# PDOC.net
KiCad netlist of a schematic drawn in Altium Designer
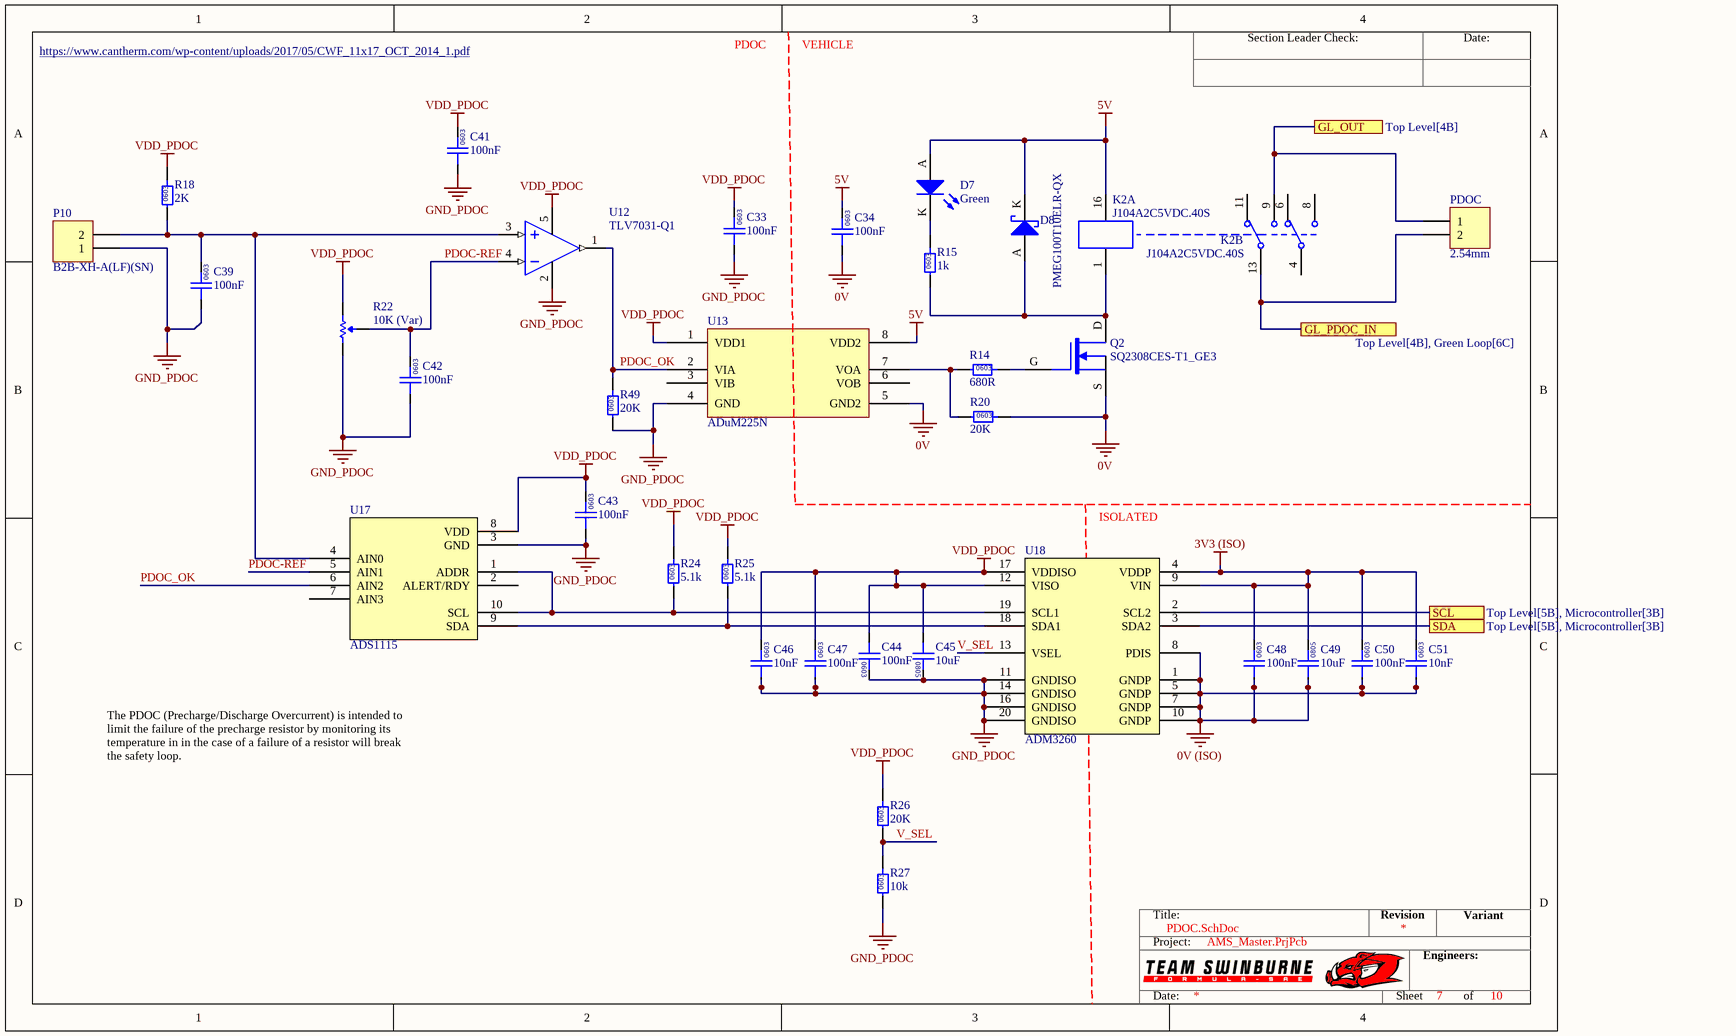
[diagram p0: PDOC.SchDoc]

(export (version "E")
  (design (tool "Eeschema 10.0.6"))
  (components
    (comp (ref "C33")
      (value "100nF")
      (footprint "0603")
      (fields
        (field (name "PART NUMBER") "CL10B104KC8NNNC")
        (field (name "MANUFACTURER") "Samsung Electro-Mechanics")
        (field (name "TOLERANCE") "±10%")
      )
      (libsource (lib "ts_standard_library") (part "Capacitor 0603"))
    )
    (comp (ref "C34")
      (value "100nF")
      (footprint "0603")
      (fields
        (field (name "PART NUMBER") "CL10B104KC8NNNC")
        (field (name "MANUFACTURER") "Samsung Electro-Mechanics")
        (field (name "TOLERANCE") "±10%")
      )
      (libsource (lib "ts_standard_library") (part "Capacitor 0603"))
    )
    (comp (ref "C39")
      (value "100nF")
      (footprint "0603")
      (fields
        (field (name "PART NUMBER") "GCM188L81H104KA57D")
        (field (name "MANUFACTURER") "muRata")
        (field (name "TOLERANCE") "±10%")
      )
      (libsource (lib "ts_standard_library") (part "Capacitor 0603"))
    )
    (comp (ref "C41")
      (value "100nF")
      (footprint "0603")
      (fields
        (field (name "PART NUMBER") "GCM188L81H104KA57D")
        (field (name "MANUFACTURER") "muRata")
        (field (name "TOLERANCE") "±10%")
      )
      (libsource (lib "ts_standard_library") (part "Capacitor 0603"))
    )
    (comp (ref "C42")
      (value "100nF")
      (footprint "0603")
      (fields
        (field (name "PART NUMBER") "GCM188L81H104KA57D")
        (field (name "MANUFACTURER") "muRata")
        (field (name "TOLERANCE") "±10%")
      )
      (libsource (lib "ts_standard_library") (part "Capacitor 0603"))
    )
    (comp (ref "C43")
      (value "100nF")
      (footprint "0603")
      (fields
        (field (name "PART NUMBER") "GCM188L81H104KA57D")
        (field (name "MANUFACTURER") "muRata")
        (field (name "TOLERANCE") "±10%")
      )
      (libsource (lib "ts_standard_library") (part "Capacitor 0603"))
    )
    (comp (ref "C44")
      (value "100nF")
      (footprint "0603")
      (fields
        (field (name "PART NUMBER") "GCM188L81H104KA57D")
        (field (name "MANUFACTURER") "muRata")
        (field (name "TOLERANCE") "±10%")
      )
      (libsource (lib "ts_standard_library") (part "Capacitor 0603"))
    )
    (comp (ref "C45")
      (value "10uF")
      (footprint "0805")
      (fields
        (field (name "PART NUMBER") "GRM21BR6YA106KE43L")
        (field (name "MANUFACTURER") "muRata")
        (field (name "TOLERANCE") "10%")
      )
      (libsource (lib "ts_standard_library") (part "Capacitor 0805"))
    )
    (comp (ref "C46")
      (value "10nF")
      (footprint "0603")
      (fields
        (field (name "PART NUMBER") "GCM188L81H103KA03D")
        (field (name "MANUFACTURER") "muRata")
        (field (name "TOLERANCE") "±10%")
      )
      (libsource (lib "ts_standard_library") (part "Capacitor 0603"))
    )
    (comp (ref "C47")
      (value "100nF")
      (footprint "0603")
      (fields
        (field (name "PART NUMBER") "GCM188L81H104KA57D")
        (field (name "MANUFACTURER") "muRata")
        (field (name "TOLERANCE") "±10%")
      )
      (libsource (lib "ts_standard_library") (part "Capacitor 0603"))
    )
    (comp (ref "C48")
      (value "100nF")
      (footprint "0603")
      (fields
        (field (name "PART NUMBER") "GCM188L81H104KA57D")
        (field (name "MANUFACTURER") "muRata")
        (field (name "TOLERANCE") "±10%")
      )
      (libsource (lib "ts_standard_library") (part "Capacitor 0603"))
    )
    (comp (ref "C49")
      (value "10uF")
      (footprint "0805")
      (fields
        (field (name "PART NUMBER") "GRM21BR6YA106KE43L")
        (field (name "MANUFACTURER") "muRata")
        (field (name "TOLERANCE") "10%")
      )
      (libsource (lib "ts_standard_library") (part "Capacitor 0805"))
    )
    (comp (ref "C50")
      (value "100nF")
      (footprint "0603")
      (fields
        (field (name "PART NUMBER") "GCM188L81H104KA57D")
        (field (name "MANUFACTURER") "muRata")
        (field (name "TOLERANCE") "±10%")
      )
      (libsource (lib "ts_standard_library") (part "Capacitor 0603"))
    )
    (comp (ref "C51")
      (value "10nF")
      (footprint "0603")
      (fields
        (field (name "PART NUMBER") "GCM188L81H103KA03D")
        (field (name "MANUFACTURER") "muRata")
        (field (name "TOLERANCE") "±10%")
      )
      (libsource (lib "ts_standard_library") (part "Capacitor 0603"))
    )
    (comp (ref "D7")
      (value "Green")
      (footprint "0805 LED")
      (description "Green LED Indication - Discrete 1.75V 0805 (2012 Metric)")
      (fields (field (name "PART NUMBER") "SML-210FTT86") (field (name "MANUFACTURER") "ROHM Semiconductor"))
      (libsource (lib "ts_20-standard-library") (part "LED"))
    )
    (comp (ref "D8")
      (value "PMEG100T10ELR-QX")
      (footprint "NXP SOD123W")
      (fields
        (field (name "MANUFACTURER") "Nexperia USA Inc.")
        (field (name "DIGIKEY PART NUMBER") "1727-PMEG100T10ELR-QXCT-ND")
      )
      (libsource (lib "ts_standard_library") (part "Diode (Schottky)"))
    )
    (comp (ref "K2")
      (value "J104A2C5VDC.40S")
      (footprint "TI 2-DIL")
      (description "RELAY GEN PURPOSE DPDT 3A 5V")
      (fields
        (field (name "MANUFACTURER") "CIT Relay and Switch")
        (field (name "DIGIKEY PART NUMBER") "2449-J104A2C5VDC.40S-ND")
      )
      (libsource (lib "") (part "J104A2C5VDC.40S_1"))
    )
    (comp (ref "P10")
      (value "B2B-XH-A(LF)(SN)")
      (footprint "XH 2 PIN VERT")
      (fields (field (name "DIGIKEY PART NUMBER") "455-2247-ND") (field (name "CONTACT") "Tin"))
      (libsource (lib "ts_standard_connectors") (part "Header 1x2"))
    )
    (comp (ref "PDOC")
      (value "2.54mm")
      (footprint "TH 2.54mm Header 1x2")
      (fields (field (name "PART NUMBER") "TH 2.54mm Header 1x2") (field (name "CONTACT") "NA"))
      (libsource (lib "") (part "Header 1x2_1"))
    )
    (comp (ref "Q2")
      (value "SQ2308CES-T1_GE3")
      (footprint "VSHY SOT-23-3")
      (description "MOSFET N-CH 60V 2.3A SOT23")
      (fields
        (field (name "MANUFACTURER") "Vishay Siliconix")
        (field (name "DIGIKEY PART NUMBER") "SQ2308CES-T1_GE3CT-ND")
        (field (name "PUBLISHER") "Altium Limited")
      )
      (libsource (lib "ts_standard_library") (part "MOSFET-N"))
    )
    (comp (ref "R14")
      (value "680R")
      (footprint "0603")
      (fields
        (field (name "PART NUMBER") "RC0603JR-13680RL")
        (field (name "MANUFACTURER") "YAGEO")
        (field (name "TOLERANCE") "0.01")
      )
      (libsource (lib "ts_standard_library") (part "Resistor 0603"))
    )
    (comp (ref "R15")
      (value "1k")
      (footprint "0603")
      (fields
        (field (name "PART NUMBER") "RC0603FR-071KL")
        (field (name "MANUFACTURER") "YAGEO")
        (field (name "TOLERANCE") "0.01")
      )
      (libsource (lib "ts_standard_library") (part "Resistor 0603"))
    )
    (comp (ref "R18")
      (value "2K")
      (footprint "0603")
      (fields
        (field (name "PART NUMBER") "RC0603FR-072KL")
        (field (name "MANUFACTURER") "YAGEO")
        (field (name "TOLERANCE") "0.01")
      )
      (libsource (lib "ts_standard_library") (part "Resistor 0603"))
    )
    (comp (ref "R20")
      (value "20K")
      (footprint "0603")
      (fields
        (field (name "PART NUMBER") "RC0603FR-0720KL")
        (field (name "MANUFACTURER") "YAGEO")
        (field (name "TOLERANCE") "0.01")
      )
      (libsource (lib "ts_standard_library") (part "Resistor 0603"))
    )
    (comp (ref "R22")
      (value "10K (Var)")
      (footprint "B 3296")
      (fields
        (field (name "PART NUMBER") "3296W-1-103LF")
        (field (name "MANUFACTURER") "Bournes Inc")
        (field (name "TOLERANCE") "0.1")
      )
      (libsource (lib "ts_standard_library") (part "Resistor (Potentiometer)"))
    )
    (comp (ref "R24")
      (value "5.1k")
      (footprint "0603")
      (fields
        (field (name "PART NUMBER") "RC0603JR-075K1L")
        (field (name "MANUFACTURER") "YAGEO")
        (field (name "TOLERANCE") "0.01")
      )
      (libsource (lib "ts_standard_library") (part "Resistor 0603"))
    )
    (comp (ref "R25")
      (value "5.1k")
      (footprint "0603")
      (fields
        (field (name "PART NUMBER") "RC0603JR-075K1L")
        (field (name "MANUFACTURER") "YAGEO")
        (field (name "TOLERANCE") "0.01")
      )
      (libsource (lib "ts_standard_library") (part "Resistor 0603"))
    )
    (comp (ref "R26")
      (value "20K")
      (footprint "0603")
      (fields
        (field (name "PART NUMBER") "RC0603FR-0720KL")
        (field (name "MANUFACTURER") "YAGEO")
        (field (name "TOLERANCE") "0.01")
      )
      (libsource (lib "ts_standard_library") (part "Resistor 0603"))
    )
    (comp (ref "R27")
      (value "10k")
      (footprint "0603")
      (fields
        (field (name "PART NUMBER") "RC0603FR-0710KL")
        (field (name "MANUFACTURER") "YAGEO")
        (field (name "TOLERANCE") "0.01")
      )
      (libsource (lib "ts_standard_library") (part "Resistor 0603"))
    )
    (comp (ref "R49")
      (value "20K")
      (footprint "0603")
      (fields
        (field (name "PART NUMBER") "RC0603FR-0720KL")
        (field (name "MANUFACTURER") "YAGEO")
        (field (name "TOLERANCE") "0.01")
      )
      (libsource (lib "ts_standard_library") (part "Resistor 0603"))
    )
    (comp (ref "U12")
      (value "TLV7031-Q1")
      (footprint "TI SOT-23-5")
      (fields
        (field (name "MANUFACTURER") "Texas Instruments")
        (field (name "DIGIKEY PART NUMBER") "296-TLV7031QDBVRQ1CT-ND")
      )
      (libsource (lib "ts_standard_library") (part "TLV7031-Q1"))
    )
    (comp (ref "U13")
      (value "ADuM225N")
      (footprint "AD-SOIC-8W")
      (description "DIGITAL ISOLATOR, DUAL CHANNEL")
      (fields (field (name "MANUFACTURER") "Analogue Devices"))
      (libsource (lib "ts_standard_library") (part "ADuM225N"))
    )
    (comp (ref "U17")
      (value "ADS1115")
      (footprint "TI 10-VSSOP")
      (description "16 Bit Analog to Digital Converter 2, 4 Input 1 Sigma-Delta 10-VSSOP")
      (fields
        (field (name "MANUFACTURER") "Texas Instruments")
        (field (name "DIGIKEY PART NUMBER") "296-38849-1-ND")
      )
      (libsource (lib "ts_standard_library") (part "ADS1115"))
    )
    (comp (ref "U18")
      (value "ADM3260")
      (footprint "AD 20-SSOP")
      (description "I²C Digital Isolator 2500Vrms 2 Channel 25kV/µs CMTI 20-SSOP (0.209\", 5.30mm Width)")
      (libsource (lib "Team Swinburne") (part "ADM3260"))
    )
  )
  (nets
    (net (code "1") (name "/GL_OUT") (class "Default")
      (node (ref "K2") (pin "9") (pinfunction "9_9") (pintype "passive"))
      (node (ref "PDOC") (pin "1") (pinfunction "1_1") (pintype "passive"))
    )
    (net (code "2") (name "/GL_PDOC_IN") (class "Default")
      (node (ref "K2") (pin "13") (pinfunction "13_13") (pintype "passive"))
      (node (ref "PDOC") (pin "2") (pinfunction "2_2") (pintype "passive"))
    )
    (net (code "3") (name "/PDOC-REF") (class "Default")
      (node (ref "C42") (pin "2") (pinfunction "2_2") (pintype "passive"))
      (node (ref "R22") (pin "2") (pinfunction "Wiper_2") (pintype "passive"))
      (node (ref "U12") (pin "4") (pinfunction "IN-_4") (pintype "input"))
      (node (ref "U17") (pin "5") (pinfunction "AIN1_5") (pintype "passive"))
    )
    (net (code "4") (name "/PDOC_OK") (class "Default")
      (node (ref "R49") (pin "2") (pinfunction "2_2") (pintype "passive"))
      (node (ref "U12") (pin "1") (pinfunction "OUT_1") (pintype "output"))
      (node (ref "U13") (pin "2") (pinfunction "VIA_2") (pintype "passive"))
      (node (ref "U17") (pin "6") (pinfunction "AIN2_6") (pintype "passive"))
    )
    (net (code "5") (name "/SCL") (class "Default")
      (node (ref "U18") (pin "2") (pinfunction "SCL2_2") (pintype "passive"))
    )
    (net (code "6") (name "/SDA") (class "Default")
      (node (ref "U18") (pin "3") (pinfunction "SDA2_3") (pintype "passive"))
    )
    (net (code "7") (name "/V_SEL") (class "Default")
      (node (ref "R26") (pin "1") (pinfunction "1_1") (pintype "passive"))
      (node (ref "R27") (pin "2") (pinfunction "2_2") (pintype "passive"))
      (node (ref "U18") (pin "13") (pinfunction "VSEL_13") (pintype "passive"))
    )
    (net (code "8") (name "0V") (class "Default")
      (node (ref "C34") (pin "1") (pinfunction "1_1") (pintype "passive"))
      (node (ref "Q2") (pin "S") (pinfunction "S_S") (pintype "passive"))
      (node (ref "R20") (pin "2") (pinfunction "2_2") (pintype "passive"))
      (node (ref "U13") (pin "5") (pinfunction "GND2_5") (pintype "passive"))
    )
    (net (code "9") (name "0V (ISO)") (class "Default")
      (node (ref "C48") (pin "1") (pinfunction "1_1") (pintype "passive"))
      (node (ref "C49") (pin "1") (pinfunction "1_1") (pintype "passive"))
      (node (ref "C50") (pin "1") (pinfunction "1_1") (pintype "passive"))
      (node (ref "C51") (pin "1") (pinfunction "1_1") (pintype "passive"))
      (node (ref "U18") (pin "1") (pinfunction "GNDP_1") (pintype "passive"))
      (node (ref "U18") (pin "10") (pinfunction "GNDP_10") (pintype "passive"))
      (node (ref "U18") (pin "5") (pinfunction "GNDP_5") (pintype "passive"))
      (node (ref "U18") (pin "7") (pinfunction "GNDP_7") (pintype "passive"))
      (node (ref "U18") (pin "8") (pinfunction "PDIS_8") (pintype "passive"))
    )
    (net (code "10") (name "3V3 (ISO)") (class "Default")
      (node (ref "C48") (pin "2") (pinfunction "2_2") (pintype "passive"))
      (node (ref "C49") (pin "2") (pinfunction "2_2") (pintype "passive"))
      (node (ref "C50") (pin "2") (pinfunction "2_2") (pintype "passive"))
      (node (ref "C51") (pin "2") (pinfunction "2_2") (pintype "passive"))
      (node (ref "U18") (pin "4") (pinfunction "VDDP_4") (pintype "passive"))
      (node (ref "U18") (pin "9") (pinfunction "VIN_9") (pintype "passive"))
    )
    (net (code "11") (name "5V") (class "Default")
      (node (ref "C34") (pin "2") (pinfunction "2_2") (pintype "passive"))
      (node (ref "D7") (pin "A") (pinfunction "A_A") (pintype "passive"))
      (node (ref "D8") (pin "K") (pinfunction "K_K") (pintype "passive"))
      (node (ref "K2") (pin "16") (pinfunction "16_16") (pintype "passive"))
      (node (ref "U13") (pin "8") (pinfunction "VDD2_8") (pintype "passive"))
    )
    (net (code "12") (name "GND_PDOC") (class "Default")
      (node (ref "C33") (pin "1") (pinfunction "1_1") (pintype "passive"))
      (node (ref "C39") (pin "1") (pinfunction "1_1") (pintype "passive"))
      (node (ref "C41") (pin "1") (pinfunction "1_1") (pintype "passive"))
      (node (ref "C42") (pin "1") (pinfunction "1_1") (pintype "passive"))
      (node (ref "C43") (pin "1") (pinfunction "1_1") (pintype "passive"))
      (node (ref "C44") (pin "2") (pinfunction "2_2") (pintype "passive"))
      (node (ref "C45") (pin "2") (pinfunction "2_2") (pintype "passive"))
      (node (ref "C46") (pin "1") (pinfunction "1_1") (pintype "passive"))
      (node (ref "C47") (pin "1") (pinfunction "1_1") (pintype "passive"))
      (node (ref "P10") (pin "1") (pinfunction "1_1") (pintype "passive"))
      (node (ref "R22") (pin "3") (pinfunction "CW_3") (pintype "passive"))
      (node (ref "R27") (pin "1") (pinfunction "1_1") (pintype "passive"))
      (node (ref "R49") (pin "1") (pinfunction "1_1") (pintype "passive"))
      (node (ref "U12") (pin "2") (pinfunction "V-_2") (pintype "power_in"))
      (node (ref "U13") (pin "4") (pinfunction "GND_4") (pintype "passive"))
      (node (ref "U17") (pin "3") (pinfunction "GND_3") (pintype "passive"))
      (node (ref "U18") (pin "11") (pinfunction "GNDISO_11") (pintype "passive"))
      (node (ref "U18") (pin "14") (pinfunction "GNDISO_14") (pintype "passive"))
      (node (ref "U18") (pin "16") (pinfunction "GNDISO_16") (pintype "passive"))
      (node (ref "U18") (pin "20") (pinfunction "GNDISO_20") (pintype "passive"))
    )
    (net (code "13") (name "Net-(D7-PadK)") (class "Default")
      (node (ref "D7") (pin "K") (pinfunction "K_K") (pintype "passive"))
      (node (ref "R15") (pin "2") (pinfunction "2_2") (pintype "passive"))
    )
    (net (code "14") (name "Net-(D8-PadA)") (class "Default")
      (node (ref "D8") (pin "A") (pinfunction "A_A") (pintype "passive"))
      (node (ref "K2") (pin "1") (pinfunction "1_1") (pintype "passive"))
      (node (ref "Q2") (pin "D") (pinfunction "D_D") (pintype "passive"))
      (node (ref "R15") (pin "1") (pinfunction "1_1") (pintype "passive"))
    )
    (net (code "15") (name "Net-(Q2-PadG)") (class "Default")
      (node (ref "Q2") (pin "G") (pinfunction "G_G") (pintype "passive"))
      (node (ref "R14") (pin "2") (pinfunction "2_2") (pintype "passive"))
    )
    (net (code "16") (name "Net-(U12-IN+)") (class "Default")
      (node (ref "C39") (pin "2") (pinfunction "2_2") (pintype "passive"))
      (node (ref "P10") (pin "2") (pinfunction "2_2") (pintype "passive"))
      (node (ref "R18") (pin "1") (pinfunction "1_1") (pintype "passive"))
      (node (ref "U12") (pin "3") (pinfunction "IN+_3") (pintype "input"))
      (node (ref "U17") (pin "4") (pinfunction "AIN0_4") (pintype "passive"))
    )
    (net (code "17") (name "Net-(U13-VOA)") (class "Default")
      (node (ref "R14") (pin "1") (pinfunction "1_1") (pintype "passive"))
      (node (ref "R20") (pin "1") (pinfunction "1_1") (pintype "passive"))
      (node (ref "U13") (pin "7") (pinfunction "VOA_7") (pintype "passive"))
    )
    (net (code "18") (name "Net-(U17-ADDR)") (class "Default")
      (node (ref "R24") (pin "1") (pinfunction "1_1") (pintype "passive"))
      (node (ref "U17") (pin "1") (pinfunction "ADDR_1") (pintype "passive"))
      (node (ref "U17") (pin "10") (pinfunction "SCL_10") (pintype "passive"))
      (node (ref "U18") (pin "19") (pinfunction "SCL1_19") (pintype "passive"))
    )
    (net (code "19") (name "Net-(U17-SDA)") (class "Default")
      (node (ref "R25") (pin "1") (pinfunction "1_1") (pintype "passive"))
      (node (ref "U17") (pin "9") (pinfunction "SDA_9") (pintype "passive"))
      (node (ref "U18") (pin "18") (pinfunction "SDA1_18") (pintype "passive"))
    )
    (net (code "20") (name "VDD_PDOC") (class "Default")
      (node (ref "C33") (pin "2") (pinfunction "2_2") (pintype "passive"))
      (node (ref "C41") (pin "2") (pinfunction "2_2") (pintype "passive"))
      (node (ref "C43") (pin "2") (pinfunction "2_2") (pintype "passive"))
      (node (ref "C44") (pin "1") (pinfunction "1_1") (pintype "passive"))
      (node (ref "C45") (pin "1") (pinfunction "1_1") (pintype "passive"))
      (node (ref "C46") (pin "2") (pinfunction "2_2") (pintype "passive"))
      (node (ref "C47") (pin "2") (pinfunction "2_2") (pintype "passive"))
      (node (ref "R18") (pin "2") (pinfunction "2_2") (pintype "passive"))
      (node (ref "R22") (pin "1") (pinfunction "CCW_1") (pintype "passive"))
      (node (ref "R24") (pin "2") (pinfunction "2_2") (pintype "passive"))
      (node (ref "R25") (pin "2") (pinfunction "2_2") (pintype "passive"))
      (node (ref "R26") (pin "2") (pinfunction "2_2") (pintype "passive"))
      (node (ref "U12") (pin "5") (pinfunction "Vcc_5") (pintype "power_in"))
      (node (ref "U13") (pin "1") (pinfunction "VDD1_1") (pintype "passive"))
      (node (ref "U17") (pin "8") (pinfunction "VDD_8") (pintype "passive"))
      (node (ref "U18") (pin "12") (pinfunction "VISO_12") (pintype "passive"))
      (node (ref "U18") (pin "17") (pinfunction "VDDISO_17") (pintype "passive"))
    )
    (net (code "21") (name "unconnected-(K2-Pad4)") (class "Default")
      (node (ref "K2") (pin "4") (pinfunction "4_4") (pintype "passive"))
    )
    (net (code "22") (name "unconnected-(K2-Pad6)") (class "Default")
      (node (ref "K2") (pin "6") (pinfunction "6_6") (pintype "passive"))
    )
    (net (code "23") (name "unconnected-(K2-Pad8)") (class "Default")
      (node (ref "K2") (pin "8") (pinfunction "8_8") (pintype "passive"))
    )
    (net (code "24") (name "unconnected-(K2-Pad11)") (class "Default")
      (node (ref "K2") (pin "11") (pinfunction "11_11") (pintype "passive"))
    )
    (net (code "25") (name "unconnected-(U13-VIB-Pad3)") (class "Default")
      (node (ref "U13") (pin "3") (pinfunction "VIB_3") (pintype "passive"))
    )
    (net (code "26") (name "unconnected-(U13-VOB-Pad6)") (class "Default")
      (node (ref "U13") (pin "6") (pinfunction "VOB_6") (pintype "passive"))
    )
    (net (code "27") (name "unconnected-(U17-AIN3-Pad7)") (class "Default")
      (node (ref "U17") (pin "7") (pinfunction "AIN3_7") (pintype "passive"))
    )
    (net (code "28") (name "unconnected-(U17-ALERT{slash}RDY-Pad2)") (class "Default")
      (node (ref "U17") (pin "2") (pinfunction "ALERT/RDY_2") (pintype "passive"))
    )
  )
)
